# DC-DC-converter-5A_test.net
KiCad netlist of a schematic drawn in Altium Designer
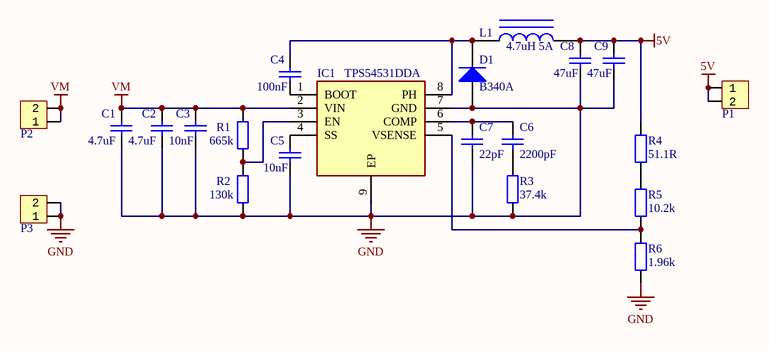
[diagram p0: DC-DC-converter-5A_test.SchDoc]

(export (version "E")
  (design (tool "Eeschema 10.0.6"))
  (components
    (comp (ref "C1")
      (value "4.7uF")
      (footprint "CAP-0603")
      (description "贴片电容")
      (libsource (lib "Power_Lib_Altium") (part "CAP"))
    )
    (comp (ref "C2")
      (value "4.7uF")
      (footprint "CAP-0603")
      (description "贴片电容")
      (libsource (lib "Power_Lib_Altium") (part "CAP"))
    )
    (comp (ref "C3")
      (value "10nF")
      (footprint "CAP-0603")
      (description "贴片电容")
      (libsource (lib "Power_Lib_Altium") (part "CAP"))
    )
    (comp (ref "C4")
      (value "100nF")
      (footprint "CAP-0603")
      (description "贴片电容")
      (libsource (lib "Power_Lib_Altium") (part "CAP"))
    )
    (comp (ref "C5")
      (value "10nF")
      (footprint "CAP-0603")
      (description "贴片电容")
      (libsource (lib "Power_Lib_Altium") (part "CAP"))
    )
    (comp (ref "C6")
      (value "2200pF")
      (footprint "CAP-0603")
      (description "贴片电容")
      (libsource (lib "Power_Lib_Altium") (part "CAP"))
    )
    (comp (ref "C7")
      (value "22pF")
      (footprint "CAP-0603")
      (description "贴片电容")
      (libsource (lib "Power_Lib_Altium") (part "CAP"))
    )
    (comp (ref "C8")
      (value "47uF")
      (footprint "CAP-0603")
      (description "贴片电容")
      (libsource (lib "Power_Lib_Altium") (part "CAP"))
    )
    (comp (ref "C9")
      (value "47uF")
      (footprint "CAP-0603")
      (description "贴片电容")
      (libsource (lib "Power_Lib_Altium") (part "CAP"))
    )
    (comp (ref "D1")
      (value "B340A")
      (footprint "DO-214AC_SMA")
      (description "肖特基二极管")
      (libsource (lib "Power_Lib_Altium") (part "DIODE"))
    )
    (comp (ref "IC1")
      (value "TPS54531DDA")
      (footprint "SOIC_8_PAD")
      (description "集成稳压芯片")
      (fields (field (name "MOUSER PART NUMBER") "595-TPS54531DDA"))
      (libsource (lib "Power_Lib_Altium") (part "TPS54531DDA"))
    )
    (comp (ref "L1")
      (value "4.7uH 5A")
      (footprint "L-10040")
      (description "电感")
      (libsource (lib "Power_Lib_Altium") (part "INDUCTOR"))
    )
    (comp (ref "P1")
      (value "HDR1x2_2.54")
      (footprint "HDR1X2_2.54_180")
      (description "Header")
      (libsource (lib "") (part "HDR1x2_2.54_1"))
    )
    (comp (ref "P2")
      (value "HDR1x2_2.54")
      (footprint "HDR1X2_2.54_180")
      (description "Header")
      (libsource (lib "Power_Lib_Altium") (part "HDR1x2_2.54"))
    )
    (comp (ref "P3")
      (value "HDR1x2_2.54")
      (footprint "HDR1X2_2.54_180")
      (description "Header")
      (libsource (lib "Power_Lib_Altium") (part "HDR1x2_2.54"))
    )
    (comp (ref "R1")
      (value "665k")
      (footprint "R-0603")
      (description "贴片电阻")
      (libsource (lib "Power_Lib_Altium") (part "RES"))
    )
    (comp (ref "R2")
      (value "130k")
      (footprint "R-0603")
      (description "贴片电阻")
      (libsource (lib "Power_Lib_Altium") (part "RES"))
    )
    (comp (ref "R3")
      (value "37.4k")
      (footprint "R-0603")
      (description "贴片电阻")
      (libsource (lib "Power_Lib_Altium") (part "RES"))
    )
    (comp (ref "R4")
      (value "51.1R")
      (footprint "R-0603")
      (description "贴片电阻")
      (libsource (lib "Power_Lib_Altium") (part "RES"))
    )
    (comp (ref "R5")
      (value "10.2k")
      (footprint "R-0603")
      (description "贴片电阻")
      (libsource (lib "Power_Lib_Altium") (part "RES"))
    )
    (comp (ref "R6")
      (value "1.96k")
      (footprint "R-0603")
      (description "贴片电阻")
      (libsource (lib "Power_Lib_Altium") (part "RES"))
    )
  )
  (nets
    (net (code "1") (name "5V") (class "Default")
      (node (ref "C8") (pin "2") (pinfunction "2_2") (pintype "passive"))
      (node (ref "C9") (pin "2") (pinfunction "2_2") (pintype "passive"))
      (node (ref "L1") (pin "2") (pinfunction "2_2") (pintype "passive"))
      (node (ref "P1") (pin "1") (pinfunction "1_1") (pintype "passive"))
      (node (ref "P1") (pin "2") (pinfunction "2_2") (pintype "passive"))
      (node (ref "R4") (pin "2") (pinfunction "2_2") (pintype "passive"))
    )
    (net (code "2") (name "GND") (class "Default")
      (node (ref "C1") (pin "1") (pinfunction "1_1") (pintype "passive"))
      (node (ref "C2") (pin "1") (pinfunction "1_1") (pintype "passive"))
      (node (ref "C3") (pin "1") (pinfunction "1_1") (pintype "passive"))
      (node (ref "C5") (pin "1") (pinfunction "1_1") (pintype "passive"))
      (node (ref "C7") (pin "1") (pinfunction "1_1") (pintype "passive"))
      (node (ref "C8") (pin "1") (pinfunction "1_1") (pintype "passive"))
      (node (ref "C9") (pin "1") (pinfunction "1_1") (pintype "passive"))
      (node (ref "D1") (pin "1") (pinfunction "A_1") (pintype "passive"))
      (node (ref "IC1") (pin "7") (pinfunction "GND_7") (pintype "passive"))
      (node (ref "IC1") (pin "9") (pinfunction "EP_9") (pintype "passive"))
      (node (ref "P3") (pin "1") (pinfunction "1_1") (pintype "passive"))
      (node (ref "P3") (pin "2") (pinfunction "2_2") (pintype "passive"))
      (node (ref "R2") (pin "1") (pinfunction "1_1") (pintype "passive"))
      (node (ref "R3") (pin "1") (pinfunction "1_1") (pintype "passive"))
      (node (ref "R6") (pin "1") (pinfunction "1_1") (pintype "passive"))
    )
    (net (code "3") (name "Net-(C6-Pad1)") (class "Default")
      (node (ref "C6") (pin "1") (pinfunction "1_1") (pintype "passive"))
      (node (ref "R3") (pin "2") (pinfunction "2_2") (pintype "passive"))
    )
    (net (code "4") (name "Net-(D1-K)") (class "Default")
      (node (ref "C4") (pin "2") (pinfunction "2_2") (pintype "passive"))
      (node (ref "D1") (pin "2") (pinfunction "K_2") (pintype "passive"))
      (node (ref "IC1") (pin "8") (pinfunction "PH_8") (pintype "passive"))
      (node (ref "L1") (pin "1") (pinfunction "1_1") (pintype "passive"))
    )
    (net (code "5") (name "Net-(IC1-BOOT)") (class "Default")
      (node (ref "C4") (pin "1") (pinfunction "1_1") (pintype "passive"))
      (node (ref "IC1") (pin "1") (pinfunction "BOOT_1") (pintype "passive"))
    )
    (net (code "6") (name "Net-(IC1-COMP)") (class "Default")
      (node (ref "C6") (pin "2") (pinfunction "2_2") (pintype "passive"))
      (node (ref "C7") (pin "2") (pinfunction "2_2") (pintype "passive"))
      (node (ref "IC1") (pin "6") (pinfunction "COMP_6") (pintype "passive"))
    )
    (net (code "7") (name "Net-(IC1-EN)") (class "Default")
      (node (ref "IC1") (pin "3") (pinfunction "EN_3") (pintype "passive"))
      (node (ref "R1") (pin "1") (pinfunction "1_1") (pintype "passive"))
      (node (ref "R2") (pin "2") (pinfunction "2_2") (pintype "passive"))
    )
    (net (code "8") (name "Net-(IC1-SS)") (class "Default")
      (node (ref "C5") (pin "2") (pinfunction "2_2") (pintype "passive"))
      (node (ref "IC1") (pin "4") (pinfunction "SS_4") (pintype "passive"))
    )
    (net (code "9") (name "Net-(IC1-VSENSE)") (class "Default")
      (node (ref "IC1") (pin "5") (pinfunction "VSENSE_5") (pintype "passive"))
      (node (ref "R5") (pin "1") (pinfunction "1_1") (pintype "passive"))
      (node (ref "R6") (pin "2") (pinfunction "2_2") (pintype "passive"))
    )
    (net (code "10") (name "Net-(R4-Pad1)") (class "Default")
      (node (ref "R4") (pin "1") (pinfunction "1_1") (pintype "passive"))
      (node (ref "R5") (pin "2") (pinfunction "2_2") (pintype "passive"))
    )
    (net (code "11") (name "VM") (class "Default")
      (node (ref "C1") (pin "2") (pinfunction "2_2") (pintype "passive"))
      (node (ref "C2") (pin "2") (pinfunction "2_2") (pintype "passive"))
      (node (ref "C3") (pin "2") (pinfunction "2_2") (pintype "passive"))
      (node (ref "IC1") (pin "2") (pinfunction "VIN_2") (pintype "passive"))
      (node (ref "P2") (pin "1") (pinfunction "1_1") (pintype "passive"))
      (node (ref "P2") (pin "2") (pinfunction "2_2") (pintype "passive"))
      (node (ref "R1") (pin "2") (pinfunction "2_2") (pintype "passive"))
    )
  )
)
